# Power.net
KiCad netlist of a schematic drawn in Altium Designer
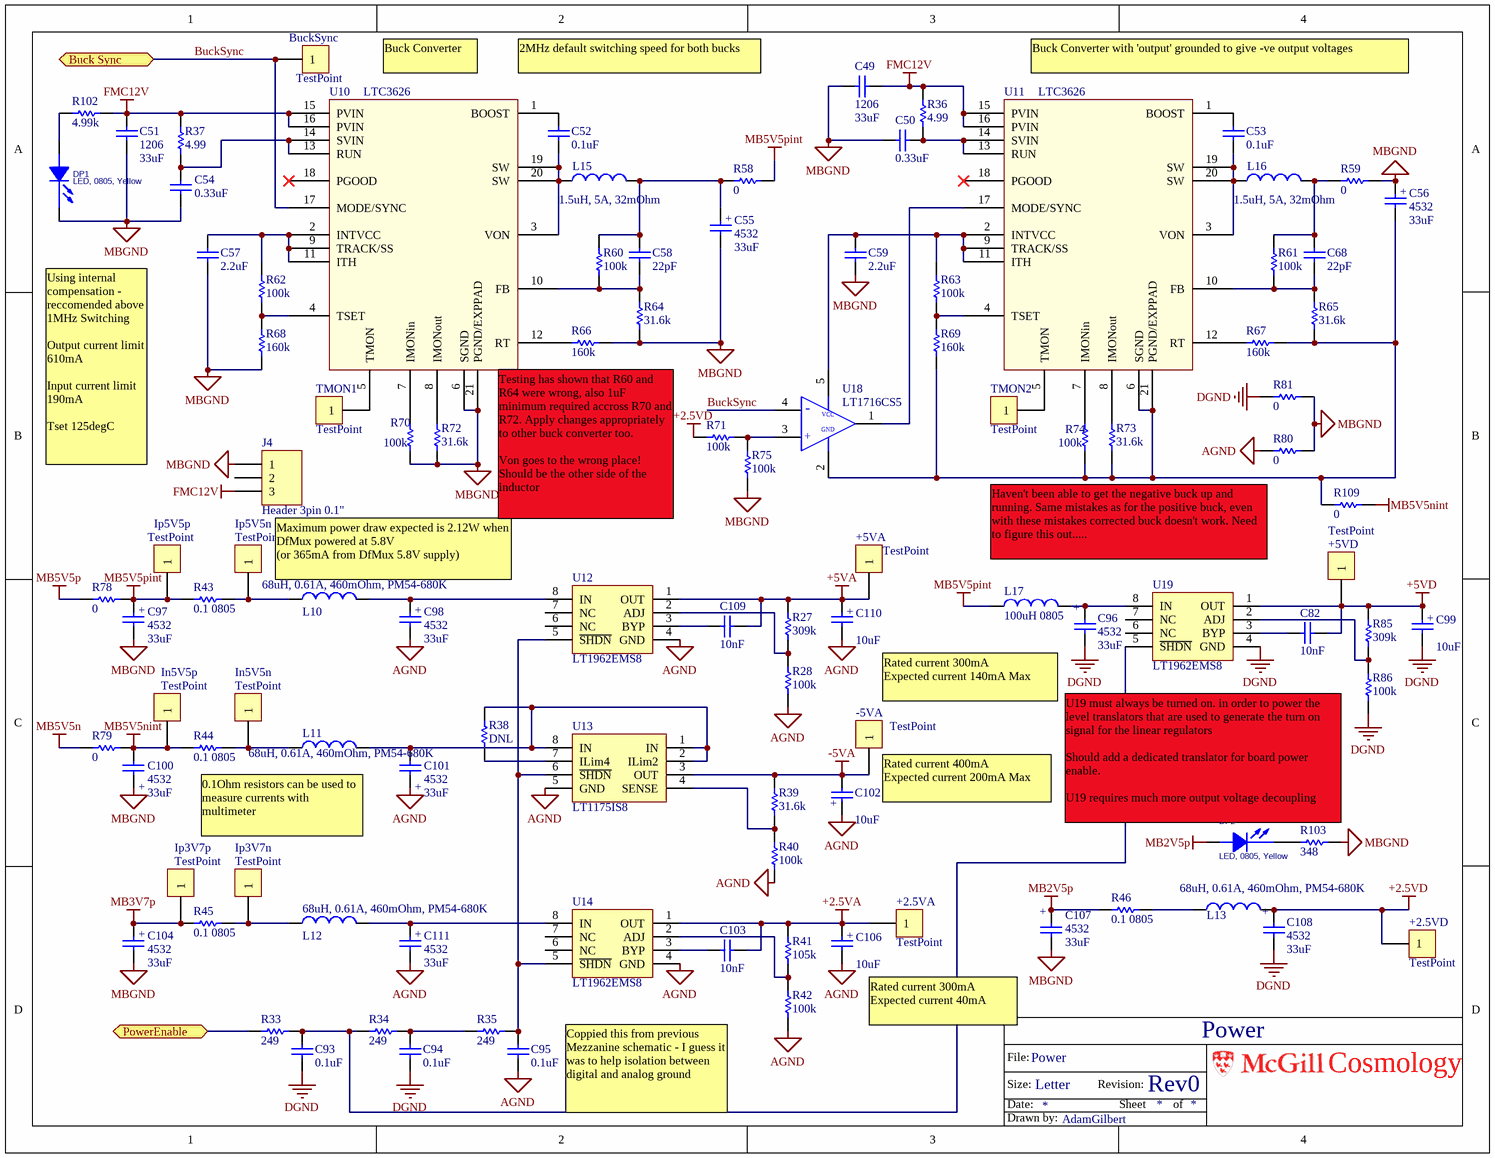
[diagram p0: Power.SchDoc]

(export (version "E")
  (design (tool "Eeschema 10.0.6"))
  (components
    (comp (ref "+2.5VA")
      (value "TestPoint")
      (footprint "TP-3520-SK")
      (description "TestPoint1")
      (libsource (lib "") (part "TestPoint_2"))
    )
    (comp (ref "+2.5VD")
      (value "TestPoint")
      (footprint "TP-3520-SK")
      (description "TestPoint1")
      (libsource (lib "") (part "TestPoint_2"))
    )
    (comp (ref "+5VA")
      (value "TestPoint")
      (footprint "TP-3520-SK")
      (description "TestPoint1")
      (libsource (lib "MGMEZZ04") (part "TestPoint"))
    )
    (comp (ref "+5VD")
      (value "TestPoint")
      (footprint "TP-3520-SK")
      (description "TestPoint1")
      (libsource (lib "MGMEZZ04") (part "TestPoint"))
    )
    (comp (ref "-5VA")
      (value "TestPoint")
      (footprint "TP-3520-SK")
      (description "TestPoint1")
      (libsource (lib "MGMEZZ04") (part "TestPoint"))
    )
    (comp (ref "BuckSync")
      (value "TestPoint")
      (footprint "TP-3520-SK")
      (description "TestPoint1")
      (libsource (lib "") (part "TestPoint_2"))
    )
    (comp (ref "C49")
      (value "33uF")
      (footprint "1206")
      (description "Capacitor, Ceramic, 1210")
      (fields
        (field (name "MANUFACTURER") "TDK Corporation")
        (field (name "MANUFACTURERS PART NUMBER") "C3216X5R1E336M")
      )
      (libsource (lib "MGMEZZ04") (part "CAP 1210"))
    )
    (comp (ref "C50")
      (value "0.33uF")
      (footprint "0603")
      (description "Capacitor, Ceramic, 0603")
      (fields (field (name "MANUFACTURER") "Generic"))
      (libsource (lib "MGMEZZ04") (part "CAP 0603"))
    )
    (comp (ref "C51")
      (value "33uF")
      (footprint "1206")
      (description "Capacitor, Ceramic, 1210")
      (fields
        (field (name "MANUFACTURER") "TDK Corporation")
        (field (name "MANUFACTURERS PART NUMBER") "C3216X5R1E336M")
      )
      (libsource (lib "MGMEZZ04") (part "CAP 1210"))
    )
    (comp (ref "C52")
      (value "0.1uF")
      (footprint "0603")
      (description "Capacitor, Ceramic, 0603")
      (fields (field (name "MANUFACTURER") "Generic"))
      (libsource (lib "MGMEZZ04") (part "CAP 0603"))
    )
    (comp (ref "C53")
      (value "0.1uF")
      (footprint "0603")
      (description "Capacitor, Ceramic, 0603")
      (fields (field (name "MANUFACTURER") "Generic"))
      (libsource (lib "MGMEZZ04") (part "CAP 0603"))
    )
    (comp (ref "C54")
      (value "0.33uF")
      (footprint "0603")
      (description "Capacitor, Ceramic, 0603")
      (fields (field (name "MANUFACTURER") "Generic"))
      (libsource (lib "MGMEZZ04") (part "CAP 0603"))
    )
    (comp (ref "C55")
      (value "33uF")
      (footprint "4532")
      (description "33u, 16V, 20%, 4532C, X5R")
      (fields
        (field (name "MANUFACTURER") "TDK Corporation")
        (field (name "MANUFACTURERS PART NUMBER") "C4532X5R1C336M")
      )
      (libsource (lib "MGMEZZ04") (part "CAP4532"))
    )
    (comp (ref "C56")
      (value "33uF")
      (footprint "4532")
      (description "33u, 16V, 20%, 4532C, X5R")
      (fields
        (field (name "MANUFACTURER") "TDK Corporation")
        (field (name "MANUFACTURERS PART NUMBER") "C4532X5R1C336M")
      )
      (libsource (lib "MGMEZZ04") (part "CAP4532"))
    )
    (comp (ref "C57")
      (value "2.2uF")
      (footprint "0603")
      (description "Capacitor, Ceramic, 0603")
      (fields (field (name "MANUFACTURER") "Generic"))
      (libsource (lib "MGMEZZ04") (part "CAP 0603"))
    )
    (comp (ref "C58")
      (value "22pF")
      (footprint "0603")
      (description "Capacitor, Ceramic, 0603")
      (fields (field (name "MANUFACTURER") "Generic"))
      (libsource (lib "MGMEZZ04") (part "CAP 0603"))
    )
    (comp (ref "C59")
      (value "2.2uF")
      (footprint "0603")
      (description "Capacitor, Ceramic, 0603")
      (fields (field (name "MANUFACTURER") "Generic"))
      (libsource (lib "MGMEZZ04") (part "CAP 0603"))
    )
    (comp (ref "C68")
      (value "22pF")
      (footprint "0603")
      (description "Capacitor, Ceramic, 0603")
      (fields (field (name "MANUFACTURER") "Generic"))
      (libsource (lib "MGMEZZ04") (part "CAP 0603"))
    )
    (comp (ref "C82")
      (value "10nF")
      (footprint "0603")
      (description "Capacitor, Ceramic, 0603")
      (fields (field (name "MANUFACTURER") "Generic"))
      (libsource (lib "MGMEZZ04") (part "CAP 0603"))
    )
    (comp (ref "C93")
      (value "0.1uF")
      (footprint "0603")
      (description "Capacitor, Ceramic, 0603")
      (fields (field (name "MANUFACTURER") "Generic"))
      (libsource (lib "MGMEZZ04") (part "CAP 0603"))
    )
    (comp (ref "C94")
      (value "0.1uF")
      (footprint "0603")
      (description "Capacitor, Ceramic, 0603")
      (fields (field (name "MANUFACTURER") "Generic"))
      (libsource (lib "MGMEZZ04") (part "CAP 0603"))
    )
    (comp (ref "C95")
      (value "0.1uF")
      (footprint "0603")
      (description "Capacitor, Ceramic, 0603")
      (fields (field (name "MANUFACTURER") "Generic"))
      (libsource (lib "MGMEZZ04") (part "CAP 0603"))
    )
    (comp (ref "C96")
      (value "33uF")
      (footprint "4532")
      (description "33u, 16V, 20%, 4532C, X5R")
      (fields
        (field (name "MANUFACTURER") "TDK Corporation")
        (field (name "MANUFACTURERS PART NUMBER") "C4532X5R1C336M")
      )
      (libsource (lib "MGMEZZ04") (part "CAP4532"))
    )
    (comp (ref "C97")
      (value "33uF")
      (footprint "4532")
      (description "33u, 16V, 20%, 4532C, X5R")
      (fields
        (field (name "MANUFACTURER") "TDK Corporation")
        (field (name "MANUFACTURERS PART NUMBER") "C4532X5R1C336M")
      )
      (libsource (lib "MGMEZZ04") (part "CAP4532"))
    )
    (comp (ref "C98")
      (value "33uF")
      (footprint "4532")
      (description "33u, 16V, 20%, 4532C, X5R")
      (fields
        (field (name "MANUFACTURER") "TDK Corporation")
        (field (name "MANUFACTURERS PART NUMBER") "C4532X5R1C336M")
      )
      (libsource (lib "MGMEZZ04") (part "CAP4532"))
    )
    (comp (ref "C99")
      (value "10uF")
      (footprint "TCASE-A")
      (description "TantA Cap")
      (fields (field (name "MANUFACTURER") "Generic"))
      (libsource (lib "MGMEZZ04") (part "CAP TANT CASE-A"))
    )
    (comp (ref "C100")
      (value "33uF")
      (footprint "4532")
      (description "33u, 16V, 20%, 4532C, X5R")
      (fields
        (field (name "MANUFACTURER") "TDK Corporation")
        (field (name "MANUFACTURERS PART NUMBER") "C4532X5R1C336M")
      )
      (libsource (lib "MGMEZZ04") (part "CAP4532"))
    )
    (comp (ref "C101")
      (value "33uF")
      (footprint "4532")
      (description "33u, 16V, 20%, 4532C, X5R")
      (fields
        (field (name "MANUFACTURER") "TDK Corporation")
        (field (name "MANUFACTURERS PART NUMBER") "C4532X5R1C336M")
      )
      (libsource (lib "MGMEZZ04") (part "CAP4532"))
    )
    (comp (ref "C102")
      (value "10uF")
      (footprint "TCASE-A")
      (description "TantA Cap")
      (fields (field (name "MANUFACTURER") "Generic"))
      (libsource (lib "MGMEZZ04") (part "CAP TANT CASE-A"))
    )
    (comp (ref "C103")
      (value "10nF")
      (footprint "0603")
      (description "Capacitor, Ceramic, 0603")
      (fields (field (name "MANUFACTURER") "Generic"))
      (libsource (lib "MGMEZZ04") (part "CAP 0603"))
    )
    (comp (ref "C104")
      (value "33uF")
      (footprint "4532")
      (description "33u, 16V, 20%, 4532C, X5R")
      (fields
        (field (name "MANUFACTURER") "TDK Corporation")
        (field (name "MANUFACTURERS PART NUMBER") "C4532X5R1C336M")
      )
      (libsource (lib "MGMEZZ04") (part "CAP4532"))
    )
    (comp (ref "C106")
      (value "10uF")
      (footprint "TCASE-A")
      (description "TantA Cap")
      (fields (field (name "MANUFACTURER") "Generic"))
      (libsource (lib "MGMEZZ04") (part "CAP TANT CASE-A"))
    )
    (comp (ref "C107")
      (value "33uF")
      (footprint "4532")
      (description "33u, 16V, 20%, 4532C, X5R")
      (fields
        (field (name "MANUFACTURER") "TDK Corporation")
        (field (name "MANUFACTURERS PART NUMBER") "C4532X5R1C336M")
      )
      (libsource (lib "MGMEZZ04") (part "CAP4532"))
    )
    (comp (ref "C108")
      (value "33uF")
      (footprint "4532")
      (description "33u, 16V, 20%, 4532C, X5R")
      (fields
        (field (name "MANUFACTURER") "TDK Corporation")
        (field (name "MANUFACTURERS PART NUMBER") "C4532X5R1C336M")
      )
      (libsource (lib "MGMEZZ04") (part "CAP4532"))
    )
    (comp (ref "C109")
      (value "10nF")
      (footprint "0603")
      (description "Capacitor, Ceramic, 0603")
      (fields (field (name "MANUFACTURER") "Generic"))
      (libsource (lib "MGMEZZ04") (part "CAP 0603"))
    )
    (comp (ref "C110")
      (value "10uF")
      (footprint "TCASE-A")
      (description "TantA Cap")
      (fields (field (name "MANUFACTURER") "Generic"))
      (libsource (lib "MGMEZZ04") (part "CAP TANT CASE-A"))
    )
    (comp (ref "C111")
      (value "33uF")
      (footprint "4532")
      (description "33u, 16V, 20%, 4532C, X5R")
      (fields
        (field (name "MANUFACTURER") "TDK Corporation")
        (field (name "MANUFACTURERS PART NUMBER") "C4532X5R1C336M")
      )
      (libsource (lib "MGMEZZ04") (part "CAP4532"))
    )
    (comp (ref "DP1")
      (value "LED, 0805, Yellow")
      (description "LED")
      (fields
        (field (name "MANUFACTURER") "Rohm Semiconductor")
        (field (name "MANUFACTURERS PART NUMBER") "SML-211YTT86")
      )
      (libsource (lib "MGMEZZ04") (part "LED, yellow, 0805, 2mA"))
    )
    (comp (ref "DP2")
      (value "LED, 0805, Yellow")
      (description "LED")
      (fields
        (field (name "MANUFACTURER") "Rohm Semiconductor")
        (field (name "MANUFACTURERS PART NUMBER") "SML-211YTT86")
      )
      (libsource (lib "MGMEZZ04") (part "LED, yellow, 0805, 2mA"))
    )
    (comp (ref "In5V5n")
      (value "TestPoint")
      (footprint "TP-3520-SK")
      (description "TestPoint1")
      (libsource (lib "MGMEZZ04") (part "TestPoint"))
    )
    (comp (ref "In5V5p")
      (value "TestPoint")
      (footprint "TP-3520-SK")
      (description "TestPoint1")
      (libsource (lib "MGMEZZ04") (part "TestPoint"))
    )
    (comp (ref "Ip3V7n")
      (value "TestPoint")
      (footprint "TP-3520-SK")
      (description "TestPoint1")
      (libsource (lib "MGMEZZ04") (part "TestPoint"))
    )
    (comp (ref "Ip3V7p")
      (value "TestPoint")
      (footprint "TP-3520-SK")
      (description "TestPoint1")
      (libsource (lib "MGMEZZ04") (part "TestPoint"))
    )
    (comp (ref "Ip5V5n")
      (value "TestPoint")
      (footprint "TP-3520-SK")
      (description "TestPoint1")
      (libsource (lib "MGMEZZ04") (part "TestPoint"))
    )
    (comp (ref "Ip5V5p")
      (value "TestPoint")
      (footprint "TP-3520-SK")
      (description "TestPoint1")
      (libsource (lib "MGMEZZ04") (part "TestPoint"))
    )
    (comp (ref "J4")
      (value "Header 3pin 0.1\"")
      (footprint "HDR1X3_MolexVertical")
      (description "Header, 0.1\"  3-Pin")
      (fields (field (name "MANUFACTURER") "Molex") (field (name "MANUFACTURERS PART NUMBER") "0099990987"))
      (libsource (lib "MGMEZZ04") (part "Header 3"))
    )
    (comp (ref "L10")
      (value "68uH")
      (footprint "CHOKEPM54")
      (description "Inductor PM54")
      (fields
        (field (name "MANUFACTURER") "Bourns Inc.")
        (field (name "MANUFACTURERS PART NUMBER") "PM54-680K")
        (field (name "PART CONSTRAINTS") "68uH, 0.61A, 460mOhm, PM54-680K")
      )
      (libsource (lib "MGMEZZ04") (part "INDPM54"))
    )
    (comp (ref "L11")
      (value "68uH")
      (footprint "CHOKEPM54")
      (description "Inductor PM54")
      (fields
        (field (name "MANUFACTURER") "Bourns Inc.")
        (field (name "MANUFACTURERS PART NUMBER") "PM54-680K")
        (field (name "PART CONSTRAINTS") "68uH, 0.61A, 460mOhm, PM54-680K")
      )
      (libsource (lib "") (part "INDPM54_1"))
    )
    (comp (ref "L12")
      (value "68uH")
      (footprint "CHOKEPM54")
      (description "Inductor PM54")
      (fields
        (field (name "MANUFACTURER") "Bourns Inc.")
        (field (name "MANUFACTURERS PART NUMBER") "PM54-680K")
        (field (name "PART CONSTRAINTS") "68uH, 0.61A, 460mOhm, PM54-680K")
      )
      (libsource (lib "MGMEZZ04") (part "INDPM54"))
    )
    (comp (ref "L13")
      (value "68uH")
      (footprint "CHOKEPM54")
      (description "Inductor PM54")
      (fields
        (field (name "MANUFACTURER") "Bourns Inc.")
        (field (name "MANUFACTURERS PART NUMBER") "PM54-680K")
        (field (name "PART CONSTRAINTS") "68uH, 0.61A, 460mOhm, PM54-680K")
      )
      (libsource (lib "") (part "INDPM54_1"))
    )
    (comp (ref "L15")
      (value "1.5uH")
      (footprint "IHLP-1212")
      (description "Inductor IHLP1212")
      (fields
        (field (name "MANUFACTURER") "Vishay Dale")
        (field (name "MANUFACTURERS PART NUMBER") "IHLP1212BZER1R5M11")
        (field (name "PART CONSTRAINTS") "1.5uH, 5A, 32mOhm")
      )
      (libsource (lib "MGMEZZ04") (part "IND IHLP1212"))
    )
    (comp (ref "L16")
      (value "1.5uH")
      (footprint "IHLP-1212")
      (description "Inductor IHLP1212")
      (fields
        (field (name "MANUFACTURER") "Vishay Dale")
        (field (name "MANUFACTURERS PART NUMBER") "IHLP1212BZER1R5M11")
        (field (name "PART CONSTRAINTS") "1.5uH, 5A, 32mOhm")
      )
      (libsource (lib "MGMEZZ04") (part "IND IHLP1212"))
    )
    (comp (ref "L17")
      (value "100uH 0805")
      (footprint "0805")
      (description "Inductor 0805")
      (fields
        (field (name "MANUFACTURER") "TDK Corporation")
        (field (name "MANUFACTURERS PART NUMBER") "GLCR2012T101M-HC")
      )
      (libsource (lib "MGMEZZ04") (part "IND 0805"))
    )
    (comp (ref "R27")
      (value "309k")
      (footprint "0603")
      (description "Resistor")
      (fields (field (name "MANUFACTURER") "Generic"))
      (libsource (lib "MGMEZZ04") (part "RES 0603"))
    )
    (comp (ref "R28")
      (value "100k")
      (footprint "0603")
      (description "Resistor")
      (fields (field (name "MANUFACTURER") "Generic"))
      (libsource (lib "MGMEZZ04") (part "RES 0603"))
    )
    (comp (ref "R33")
      (value "249")
      (footprint "0603")
      (description "Resistor")
      (fields (field (name "MANUFACTURER") "Generic"))
      (libsource (lib "MGMEZZ04") (part "RES 0603"))
    )
    (comp (ref "R34")
      (value "249")
      (footprint "0603")
      (description "Resistor")
      (fields (field (name "MANUFACTURER") "Generic"))
      (libsource (lib "MGMEZZ04") (part "RES 0603"))
    )
    (comp (ref "R35")
      (value "249")
      (footprint "0603")
      (description "Resistor")
      (fields (field (name "MANUFACTURER") "Generic"))
      (libsource (lib "MGMEZZ04") (part "RES 0603"))
    )
    (comp (ref "R36")
      (value "4.99")
      (footprint "0603")
      (description "Resistor")
      (fields (field (name "MANUFACTURER") "Generic"))
      (libsource (lib "MGMEZZ04") (part "RES 0603"))
    )
    (comp (ref "R37")
      (value "4.99")
      (footprint "0603")
      (description "Resistor")
      (fields (field (name "MANUFACTURER") "Generic"))
      (libsource (lib "MGMEZZ04") (part "RES 0603"))
    )
    (comp (ref "R38")
      (value "DNL")
      (footprint "0603")
      (description "Resistor")
      (fields (field (name "MANUFACTURER") "Generic"))
      (libsource (lib "MGMEZZ04") (part "RES 0603"))
    )
    (comp (ref "R39")
      (value "31.6k")
      (footprint "0603")
      (description "Resistor")
      (fields (field (name "MANUFACTURER") "Generic"))
      (libsource (lib "MGMEZZ04") (part "RES 0603"))
    )
    (comp (ref "R40")
      (value "100k")
      (footprint "0603")
      (description "Resistor")
      (fields (field (name "MANUFACTURER") "Generic"))
      (libsource (lib "MGMEZZ04") (part "RES 0603"))
    )
    (comp (ref "R41")
      (value "105k")
      (footprint "0603")
      (description "Resistor")
      (fields (field (name "MANUFACTURER") "Generic"))
      (libsource (lib "MGMEZZ04") (part "RES 0603"))
    )
    (comp (ref "R42")
      (value "100k")
      (footprint "0603")
      (description "Resistor")
      (fields (field (name "MANUFACTURER") "Generic"))
      (libsource (lib "MGMEZZ04") (part "RES 0603"))
    )
    (comp (ref "R43")
      (value "0.1 0805")
      (footprint "0805")
      (description "RES 0.1 OHM 1/8W 0805 SMD")
      (fields
        (field (name "MANUFACTURER") "Panasonic Electronic Components")
        (field (name "MANUFACTURERS PART NUMBER") "ERJ-L06KF10CV")
      )
      (libsource (lib "MGMEZZ04") (part "RES 0805"))
    )
    (comp (ref "R44")
      (value "0.1 0805")
      (footprint "0805")
      (description "RES 0.1 OHM 1/8W 0805 SMD")
      (fields
        (field (name "MANUFACTURER") "Panasonic Electronic Components")
        (field (name "MANUFACTURERS PART NUMBER") "ERJ-L06KF10CV")
      )
      (libsource (lib "MGMEZZ04") (part "RES 0805"))
    )
    (comp (ref "R45")
      (value "0.1 0805")
      (footprint "0805")
      (description "RES 0.1 OHM 1/8W 0805 SMD")
      (fields
        (field (name "MANUFACTURER") "Panasonic Electronic Components")
        (field (name "MANUFACTURERS PART NUMBER") "ERJ-L06KF10CV")
      )
      (libsource (lib "MGMEZZ04") (part "RES 0805"))
    )
    (comp (ref "R46")
      (value "0.1 0805")
      (footprint "0805")
      (description "RES 0.1 OHM 1/8W 0805 SMD")
      (fields
        (field (name "MANUFACTURER") "Panasonic Electronic Components")
        (field (name "MANUFACTURERS PART NUMBER") "ERJ-L06KF10CV")
      )
      (libsource (lib "MGMEZZ04") (part "RES 0805"))
    )
    (comp (ref "R58")
      (value "0")
      (footprint "0805")
      (description "RES 0.0 OHM 1/8W 0805 SMD")
      (fields (field (name "MANUFACTURER") "Generic"))
      (libsource (lib "MGMEZZ04") (part "RES 0805"))
    )
    (comp (ref "R59")
      (value "0")
      (footprint "0805")
      (description "RES 0.0 OHM 1/8W 0805 SMD")
      (fields (field (name "MANUFACTURER") "Generic"))
      (libsource (lib "MGMEZZ04") (part "RES 0805"))
    )
    (comp (ref "R60")
      (value "100k")
      (footprint "0603")
      (description "Resistor")
      (fields (field (name "MANUFACTURER") "Generic"))
      (libsource (lib "MGMEZZ04") (part "RES 0603"))
    )
    (comp (ref "R61")
      (value "100k")
      (footprint "0603")
      (description "Resistor")
      (fields (field (name "MANUFACTURER") "Generic"))
      (libsource (lib "MGMEZZ04") (part "RES 0603"))
    )
    (comp (ref "R62")
      (value "100k")
      (footprint "0603")
      (description "Resistor")
      (fields (field (name "MANUFACTURER") "Generic"))
      (libsource (lib "MGMEZZ04") (part "RES 0603"))
    )
    (comp (ref "R63")
      (value "100k")
      (footprint "0603")
      (description "Resistor")
      (fields (field (name "MANUFACTURER") "Generic"))
      (libsource (lib "MGMEZZ04") (part "RES 0603"))
    )
    (comp (ref "R64")
      (value "31.6k")
      (footprint "0603")
      (description "Resistor")
      (fields (field (name "MANUFACTURER") "Generic"))
      (libsource (lib "MGMEZZ04") (part "RES 0603"))
    )
    (comp (ref "R65")
      (value "31.6k")
      (footprint "0603")
      (description "Resistor")
      (fields (field (name "MANUFACTURER") "Generic"))
      (libsource (lib "MGMEZZ04") (part "RES 0603"))
    )
    (comp (ref "R66")
      (value "160k")
      (footprint "0603")
      (description "Resistor")
      (fields (field (name "MANUFACTURER") "Generic"))
      (libsource (lib "MGMEZZ04") (part "RES 0603"))
    )
    (comp (ref "R67")
      (value "160k")
      (footprint "0603")
      (description "Resistor")
      (fields (field (name "MANUFACTURER") "Generic"))
      (libsource (lib "MGMEZZ04") (part "RES 0603"))
    )
    (comp (ref "R68")
      (value "160k")
      (footprint "0603")
      (description "Resistor")
      (fields (field (name "MANUFACTURER") "Generic"))
      (libsource (lib "MGMEZZ04") (part "RES 0603"))
    )
    (comp (ref "R69")
      (value "160k")
      (footprint "0603")
      (description "Resistor")
      (fields (field (name "MANUFACTURER") "Generic"))
      (libsource (lib "MGMEZZ04") (part "RES 0603"))
    )
    (comp (ref "R70")
      (value "100k")
      (footprint "0603")
      (description "Resistor")
      (fields (field (name "MANUFACTURER") "Generic"))
      (libsource (lib "MGMEZZ04") (part "RES 0603"))
    )
    (comp (ref "R71")
      (value "100k")
      (footprint "0603")
      (description "Resistor")
      (fields (field (name "MANUFACTURER") "Generic"))
      (libsource (lib "MGMEZZ04") (part "RES 0603"))
    )
    (comp (ref "R72")
      (value "31.6k")
      (footprint "0603")
      (description "Resistor")
      (fields (field (name "MANUFACTURER") "Generic"))
      (libsource (lib "MGMEZZ04") (part "RES 0603"))
    )
    (comp (ref "R73")
      (value "31.6k")
      (footprint "0603")
      (description "Resistor")
      (fields (field (name "MANUFACTURER") "Generic"))
      (libsource (lib "MGMEZZ04") (part "RES 0603"))
    )
    (comp (ref "R74")
      (value "100k")
      (footprint "0603")
      (description "Resistor")
      (fields (field (name "MANUFACTURER") "Generic"))
      (libsource (lib "MGMEZZ04") (part "RES 0603"))
    )
    (comp (ref "R75")
      (value "100k")
      (footprint "0603")
      (description "Resistor")
      (fields (field (name "MANUFACTURER") "Generic"))
      (libsource (lib "MGMEZZ04") (part "RES 0603"))
    )
    (comp (ref "R78")
      (value "0")
      (footprint "0805")
      (description "RES 0.0 OHM 1/8W 0805 SMD")
      (fields (field (name "MANUFACTURER") "Generic"))
      (libsource (lib "MGMEZZ04") (part "RES 0805"))
    )
    (comp (ref "R79")
      (value "0")
      (footprint "0805")
      (description "RES 0.0 OHM 1/8W 0805 SMD")
      (fields (field (name "MANUFACTURER") "Generic"))
      (libsource (lib "MGMEZZ04") (part "RES 0805"))
    )
    (comp (ref "R80")
      (value "0")
      (footprint "1206")
      (description "RES 0.0 OHM 1/8W 1206 SMD")
      (fields (field (name "MANUFACTURER") "Generic"))
      (libsource (lib "MGMEZZ04") (part "RES 1206"))
    )
    (comp (ref "R81")
      (value "0")
      (footprint "1206")
      (description "RES 0.0 OHM 1/8W 1206 SMD")
      (fields (field (name "MANUFACTURER") "Generic"))
      (libsource (lib "MGMEZZ04") (part "RES 1206"))
    )
    (comp (ref "R85")
      (value "309k")
      (footprint "0603")
      (description "Resistor")
      (fields (field (name "MANUFACTURER") "Generic"))
      (libsource (lib "MGMEZZ04") (part "RES 0603"))
    )
    (comp (ref "R86")
      (value "100k")
      (footprint "0603")
      (description "Resistor")
      (fields (field (name "MANUFACTURER") "Generic"))
      (libsource (lib "MGMEZZ04") (part "RES 0603"))
    )
    (comp (ref "R102")
      (value "4.99k")
      (footprint "0603")
      (description "Resistor")
      (fields (field (name "MANUFACTURER") "Generic"))
      (libsource (lib "MGMEZZ04") (part "RES 0603"))
    )
    (comp (ref "R103")
      (value "348")
      (footprint "0603")
      (description "Resistor")
      (fields (field (name "MANUFACTURER") "Generic"))
      (libsource (lib "MGMEZZ04") (part "RES 0603"))
    )
    (comp (ref "R109")
      (value "0")
      (footprint "0805")
      (description "RES 0.0 OHM 1/8W 0805 SMD")
      (fields (field (name "MANUFACTURER") "Generic"))
      (libsource (lib "MGMEZZ04") (part "RES 0805"))
    )
    (comp (ref "TMON1")
      (value "TestPoint")
      (footprint "TP-3520-SK")
      (description "TestPoint1")
      (libsource (lib "") (part "TestPoint_1"))
    )
    (comp (ref "TMON2")
      (value "TestPoint")
      (footprint "TP-3520-SK")
      (description "TestPoint1")
      (libsource (lib "") (part "TestPoint_1"))
    )
    (comp (ref "U10")
      (value "LTC3626")
      (footprint "LTC3626")
      (description "20V, 2.5A Sync buck, 3Mhz")
      (fields
        (field (name "MANUFACTURERS PART NUMBER") "LTC3626EUDC#PBF")
        (field (name "MANUFACTURER") "Linear Technology")
      )
      (libsource (lib "MGMEZZ04") (part "LTC3626"))
    )
    (comp (ref "U11")
      (value "LTC3626")
      (footprint "LTC3626")
      (description "20V, 2.5A Sync buck, 3Mhz")
      (fields
        (field (name "MANUFACTURERS PART NUMBER") "LTC3626EUDC#PBF")
        (field (name "MANUFACTURER") "Linear Technology")
      )
      (libsource (lib "MGMEZZ04") (part "LTC3626"))
    )
    (comp (ref "U12")
      (value "LT1962EMS8")
      (footprint "MSOP-8")
      (description "REG, micropower, low noise, low  dropout")
      (fields
        (field (name "MANUFACTURER") "Linear Technology")
        (field (name "MANUFACTURERS PART NUMBER") "LT1962EMS8#PBF")
      )
      (libsource (lib "MGMEZZ04") (part "LT1962EMS8"))
    )
    (comp (ref "U13")
      (value "LT1175IS8")
      (footprint "SO8")
      (description "REG, negative micropower low dropout")
      (fields
        (field (name "MANUFACTURER") "Linear Technology")
        (field (name "MANUFACTURERS PART NUMBER") "LT1175IS8#PBF")
      )
      (libsource (lib "MGMEZZ04") (part "LT1175IS8"))
    )
    (comp (ref "U14")
      (value "LT1962EMS8")
      (footprint "MSOP-8")
      (description "REG, micropower, low noise, low  dropout")
      (fields
        (field (name "MANUFACTURER") "Linear Technology")
        (field (name "MANUFACTURERS PART NUMBER") "LT1962EMS8#PBF")
      )
      (libsource (lib "MGMEZZ04") (part "LT1962EMS8"))
    )
    (comp (ref "U18")
      (value "LT1716CS5")
      (footprint "SOT23-5")
      (description "Comparator 2.7V to 44V rail to rail")
      (fields
        (field (name "MANUFACTURER") "Linear Technology")
        (field (name "MANUFACTURERS PART NUMBER") "LT1716CS5#TRMPBF")
      )
      (libsource (lib "MGMEZZ04") (part "LT1716CS5"))
    )
    (comp (ref "U19")
      (value "LT1962EMS8")
      (footprint "MSOP-8")
      (description "REG, micropower, low noise, low  dropout")
      (fields
        (field (name "MANUFACTURER") "Linear Technology")
        (field (name "MANUFACTURERS PART NUMBER") "LT1962EMS8#PBF")
      )
      (libsource (lib "MGMEZZ04") (part "LT1962EMS8"))
    )
  )
  (nets
    (net (code "1") (name "+2.5VA") (class "Default")
      (node (ref "+2.5VA") (pin "1") (pinfunction "1_1") (pintype "passive"))
      (node (ref "C103") (pin "2") (pinfunction "2_2") (pintype "passive"))
      (node (ref "C106") (pin "1") (pinfunction "1_1") (pintype "passive"))
      (node (ref "R41") (pin "1") (pinfunction "1_1") (pintype "passive"))
      (node (ref "U14") (pin "1") (pinfunction "OUT_1") (pintype "power_in"))
    )
    (net (code "2") (name "+2.5VD") (class "Default")
      (node (ref "+2.5VD") (pin "1") (pinfunction "1_1") (pintype "passive"))
      (node (ref "C108") (pin "1") (pinfunction "1_1") (pintype "passive"))
      (node (ref "L13") (pin "1") (pinfunction "1_1") (pintype "passive"))
      (node (ref "R71") (pin "2") (pinfunction "2_2") (pintype "passive"))
    )
    (net (code "3") (name "+5VA") (class "Default")
      (node (ref "+5VA") (pin "1") (pinfunction "1_1") (pintype "passive"))
      (node (ref "C109") (pin "2") (pinfunction "2_2") (pintype "passive"))
      (node (ref "C110") (pin "1") (pinfunction "1_1") (pintype "passive"))
      (node (ref "R27") (pin "1") (pinfunction "1_1") (pintype "passive"))
      (node (ref "U12") (pin "1") (pinfunction "OUT_1") (pintype "power_in"))
    )
    (net (code "4") (name "+5VD") (class "Default")
      (node (ref "+5VD") (pin "1") (pinfunction "1_1") (pintype "passive"))
      (node (ref "C82") (pin "2") (pinfunction "2_2") (pintype "passive"))
      (node (ref "C99") (pin "1") (pinfunction "1_1") (pintype "passive"))
      (node (ref "R85") (pin "1") (pinfunction "1_1") (pintype "passive"))
      (node (ref "U19") (pin "1") (pinfunction "OUT_1") (pintype "power_in"))
    )
    (net (code "5") (name "-5VA") (class "Default")
      (node (ref "-5VA") (pin "1") (pinfunction "1_1") (pintype "passive"))
      (node (ref "C102") (pin "2") (pinfunction "2_2") (pintype "passive"))
      (node (ref "R39") (pin "1") (pinfunction "1_1") (pintype "passive"))
      (node (ref "U13") (pin "3") (pinfunction "OUT_3") (pintype "passive"))
    )
    (net (code "6") (name "/BuckSync") (class "Default")
      (node (ref "BuckSync") (pin "1") (pinfunction "1_1") (pintype "passive"))
      (node (ref "U10") (pin "17") (pinfunction "MODE/SYNC_17") (pintype "passive"))
      (node (ref "U18") (pin "4") (pinfunction "-_4") (pintype "power_in"))
    )
    (net (code "7") (name "/PowerEnable") (class "Default")
      (node (ref "R33") (pin "1") (pinfunction "1_1") (pintype "passive"))
    )
    (net (code "8") (name "AGND") (class "Default")
      (node (ref "C101") (pin "1") (pinfunction "1_1") (pintype "passive"))
      (node (ref "C102") (pin "1") (pinfunction "1_1") (pintype "passive"))
      (node (ref "C106") (pin "2") (pinfunction "2_2") (pintype "passive"))
      (node (ref "C110") (pin "2") (pinfunction "2_2") (pintype "passive"))
      (node (ref "C111") (pin "2") (pinfunction "2_2") (pintype "passive"))
      (node (ref "C95") (pin "2") (pinfunction "2_2") (pintype "passive"))
      (node (ref "C98") (pin "2") (pinfunction "2_2") (pintype "passive"))
      (node (ref "R28") (pin "2") (pinfunction "2_2") (pintype "passive"))
      (node (ref "R40") (pin "2") (pinfunction "2_2") (pintype "passive"))
      (node (ref "R42") (pin "2") (pinfunction "2_2") (pintype "passive"))
      (node (ref "R80") (pin "2") (pinfunction "2_2") (pintype "passive"))
      (node (ref "U12") (pin "4") (pinfunction "GND_4") (pintype "power_in"))
      (node (ref "U13") (pin "5") (pinfunction "GND_5") (pintype "passive"))
      (node (ref "U14") (pin "4") (pinfunction "GND_4") (pintype "power_in"))
    )
    (net (code "9") (name "DGND") (class "Default")
      (node (ref "C108") (pin "2") (pinfunction "2_2") (pintype "passive"))
      (node (ref "C93") (pin "1") (pinfunction "1_1") (pintype "passive"))
      (node (ref "C94") (pin "2") (pinfunction "2_2") (pintype "passive"))
      (node (ref "C96") (pin "2") (pinfunction "2_2") (pintype "passive"))
      (node (ref "C99") (pin "2") (pinfunction "2_2") (pintype "passive"))
      (node (ref "R81") (pin "2") (pinfunction "2_2") (pintype "passive"))
      (node (ref "R86") (pin "2") (pinfunction "2_2") (pintype "passive"))
      (node (ref "U19") (pin "4") (pinfunction "GND_4") (pintype "power_in"))
    )
    (net (code "10") (name "FMC12V") (class "Default")
      (node (ref "C49") (pin "1") (pinfunction "1_1") (pintype "passive"))
      (node (ref "C51") (pin "1") (pinfunction "1_1") (pintype "passive"))
      (node (ref "J4") (pin "3") (pinfunction "3_3") (pintype "passive"))
      (node (ref "R102") (pin "2") (pinfunction "2_2") (pintype "passive"))
      (node (ref "R36") (pin "2") (pinfunction "2_2") (pintype "passive"))
      (node (ref "R37") (pin "1") (pinfunction "1_1") (pintype "passive"))
      (node (ref "U10") (pin "15") (pinfunction "PVIN_15") (pintype "passive"))
      (node (ref "U10") (pin "16") (pinfunction "PVIN_16") (pintype "passive"))
      (node (ref "U11") (pin "15") (pinfunction "PVIN_15") (pintype "passive"))
      (node (ref "U11") (pin "16") (pinfunction "PVIN_16") (pintype "passive"))
    )
    (net (code "11") (name "MB2V5p") (class "Default")
      (node (ref "C107") (pin "1") (pinfunction "1_1") (pintype "passive"))
      (node (ref "DP2") (pin "1") (pinfunction "ANODE_1") (pintype "passive"))
      (node (ref "R46") (pin "1") (pinfunction "1_1") (pintype "passive"))
    )
    (net (code "12") (name "MB3V7p") (class "Default")
      (node (ref "C104") (pin "1") (pinfunction "1_1") (pintype "passive"))
      (node (ref "Ip3V7p") (pin "1") (pinfunction "1_1") (pintype "passive"))
      (node (ref "R45") (pin "1") (pinfunction "1_1") (pintype "passive"))
    )
    (net (code "13") (name "MB5V5n") (class "Default")
      (node (ref "R79") (pin "1") (pinfunction "1_1") (pintype "passive"))
    )
    (net (code "14") (name "MB5V5nint") (class "Default")
      (node (ref "C100") (pin "2") (pinfunction "2_2") (pintype "passive"))
      (node (ref "In5V5p") (pin "1") (pinfunction "1_1") (pintype "passive"))
      (node (ref "R109") (pin "1") (pinfunction "1_1") (pintype "passive"))
      (node (ref "R44") (pin "1") (pinfunction "1_1") (pintype "passive"))
      (node (ref "R79") (pin "2") (pinfunction "2_2") (pintype "passive"))
    )
    (net (code "15") (name "MB5V5p") (class "Default")
      (node (ref "R78") (pin "1") (pinfunction "1_1") (pintype "passive"))
    )
    (net (code "16") (name "MB5V5pint") (class "Default")
      (node (ref "C97") (pin "1") (pinfunction "1_1") (pintype "passive"))
      (node (ref "Ip5V5p") (pin "1") (pinfunction "1_1") (pintype "passive"))
      (node (ref "L17") (pin "1") (pinfunction "1_1") (pintype "passive"))
      (node (ref "R43") (pin "1") (pinfunction "1_1") (pintype "passive"))
      (node (ref "R58") (pin "2") (pinfunction "2_2") (pintype "passive"))
      (node (ref "R78") (pin "2") (pinfunction "2_2") (pintype "passive"))
    )
    (net (code "17") (name "MBGND") (class "Default")
      (node (ref "C100") (pin "1") (pinfunction "1_1") (pintype "passive"))
      (node (ref "C104") (pin "2") (pinfunction "2_2") (pintype "passive"))
      (node (ref "C107") (pin "2") (pinfunction "2_2") (pintype "passive"))
      (node (ref "C49") (pin "2") (pinfunction "2_2") (pintype "passive"))
      (node (ref "C50") (pin "1") (pinfunction "1_1") (pintype "passive"))
      (node (ref "C51") (pin "2") (pinfunction "2_2") (pintype "passive"))
      (node (ref "C54") (pin "1") (pinfunction "1_1") (pintype "passive"))
      (node (ref "C55") (pin "2") (pinfunction "2_2") (pintype "passive"))
      (node (ref "C56") (pin "1") (pinfunction "1_1") (pintype "passive"))
      (node (ref "C57") (pin "1") (pinfunction "1_1") (pintype "passive"))
      (node (ref "C59") (pin "1") (pinfunction "1_1") (pintype "passive"))
      (node (ref "C97") (pin "2") (pinfunction "2_2") (pintype "passive"))
      (node (ref "DP1") (pin "2") (pinfunction "CATHODE_2") (pintype "passive"))
      (node (ref "J4") (pin "1") (pinfunction "1_1") (pintype "passive"))
      (node (ref "R103") (pin "1") (pinfunction "1_1") (pintype "passive"))
      (node (ref "R59") (pin "2") (pinfunction "2_2") (pintype "passive"))
      (node (ref "R64") (pin "1") (pinfunction "1_1") (pintype "passive"))
      (node (ref "R66") (pin "1") (pinfunction "1_1") (pintype "passive"))
      (node (ref "R68") (pin "2") (pinfunction "2_2") (pintype "passive"))
      (node (ref "R70") (pin "1") (pinfunction "1_1") (pintype "passive"))
      (node (ref "R72") (pin "1") (pinfunction "1_1") (pintype "passive"))
      (node (ref "R75") (pin "2") (pinfunction "2_2") (pintype "passive"))
      (node (ref "R80") (pin "1") (pinfunction "1_1") (pintype "passive"))
      (node (ref "R81") (pin "1") (pinfunction "1_1") (pintype "passive"))
      (node (ref "U10") (pin "21") (pinfunction "PGND/EXPPAD_21") (pintype "passive"))
      (node (ref "U10") (pin "6") (pinfunction "SGND_6") (pintype "passive"))
    )
    (net (code "18") (name "Net-(C55-Pad1)") (class "Default")
      (node (ref "C55") (pin "1") (pinfunction "1_1") (pintype "passive"))
      (node (ref "C58") (pin "2") (pinfunction "2_2") (pintype "passive"))
      (node (ref "L15") (pin "2") (pinfunction "2_2") (pintype "passive"))
      (node (ref "R58") (pin "1") (pinfunction "1_1") (pintype "passive"))
      (node (ref "R60") (pin "2") (pinfunction "2_2") (pintype "passive"))
    )
    (net (code "19") (name "Net-(C68-Pad2)") (class "Default")
      (node (ref "C68") (pin "2") (pinfunction "2_2") (pintype "passive"))
      (node (ref "L16") (pin "2") (pinfunction "2_2") (pintype "passive"))
      (node (ref "R59") (pin "1") (pinfunction "1_1") (pintype "passive"))
      (node (ref "R61") (pin "2") (pinfunction "2_2") (pintype "passive"))
    )
    (net (code "20") (name "Net-(C94-Pad1)") (class "Default")
      (node (ref "C94") (pin "1") (pinfunction "1_1") (pintype "passive"))
      (node (ref "R34") (pin "2") (pinfunction "2_2") (pintype "passive"))
      (node (ref "R35") (pin "1") (pinfunction "1_1") (pintype "passive"))
    )
    (net (code "21") (name "Net-(DP1-ANODE)") (class "Default")
      (node (ref "DP1") (pin "1") (pinfunction "ANODE_1") (pintype "passive"))
      (node (ref "R102") (pin "1") (pinfunction "1_1") (pintype "passive"))
    )
    (net (code "22") (name "Net-(DP2-CATHODE)") (class "Default")
      (node (ref "DP2") (pin "2") (pinfunction "CATHODE_2") (pintype "passive"))
      (node (ref "R103") (pin "2") (pinfunction "2_2") (pintype "passive"))
    )
    (net (code "23") (name "Net-(In5V5n-Pad1)") (class "Default")
      (node (ref "In5V5n") (pin "1") (pinfunction "1_1") (pintype "passive"))
      (node (ref "L11") (pin "2") (pinfunction "2_2") (pintype "passive"))
      (node (ref "R44") (pin "2") (pinfunction "2_2") (pintype "passive"))
    )
    (net (code "24") (name "Net-(Ip3V7n-Pad1)") (class "Default")
      (node (ref "Ip3V7n") (pin "1") (pinfunction "1_1") (pintype "passive"))
      (node (ref "L12") (pin "1") (pinfunction "1_1") (pintype "passive"))
      (node (ref "R45") (pin "2") (pinfunction "2_2") (pintype "passive"))
    )
    (net (code "25") (name "Net-(Ip5V5n-Pad1)") (class "Default")
      (node (ref "Ip5V5n") (pin "1") (pinfunction "1_1") (pintype "passive"))
      (node (ref "L10") (pin "1") (pinfunction "1_1") (pintype "passive"))
      (node (ref "R43") (pin "2") (pinfunction "2_2") (pintype "passive"))
    )
    (net (code "26") (name "Net-(L13-Pad2)") (class "Default")
      (node (ref "L13") (pin "2") (pinfunction "2_2") (pintype "passive"))
      (node (ref "R46") (pin "2") (pinfunction "2_2") (pintype "passive"))
    )
    (net (code "27") (name "Net-(U10-BOOST)") (class "Default")
      (node (ref "C52") (pin "2") (pinfunction "2_2") (pintype "passive"))
      (node (ref "U10") (pin "1") (pinfunction "BOOST_1") (pintype "passive"))
    )
    (net (code "28") (name "Net-(U10-FB)") (class "Default")
      (node (ref "C58") (pin "1") (pinfunction "1_1") (pintype "passive"))
      (node (ref "R60") (pin "1") (pinfunction "1_1") (pintype "passive"))
      (node (ref "R64") (pin "2") (pinfunction "2_2") (pintype "passive"))
      (node (ref "U10") (pin "10") (pinfunction "FB_10") (pintype "passive"))
    )
    (net (code "29") (name "Net-(U10-IMONin)") (class "Default")
      (node (ref "R70") (pin "2") (pinfunction "2_2") (pintype "passive"))
      (node (ref "U10") (pin "7") (pinfunction "IMONin_7") (pintype "passive"))
    )
    (net (code "30") (name "Net-(U10-IMONout)") (class "Default")
      (node (ref "R72") (pin "2") (pinfunction "2_2") (pintype "passive"))
      (node (ref "U10") (pin "8") (pinfunction "IMONout_8") (pintype "passive"))
    )
    (net (code "31") (name "Net-(U10-INTVCC)") (class "Default")
      (node (ref "C57") (pin "2") (pinfunction "2_2") (pintype "passive"))
      (node (ref "R62") (pin "2") (pinfunction "2_2") (pintype "passive"))
      (node (ref "U10") (pin "11") (pinfunction "ITH_11") (pintype "passive"))
      (node (ref "U10") (pin "2") (pinfunction "INTVCC_2") (pintype "passive"))
      (node (ref "U10") (pin "9") (pinfunction "TRACK/SS_9") (pintype "passive"))
    )
    (net (code "32") (name "Net-(U10-RT)") (class "Default")
      (node (ref "R66") (pin "2") (pinfunction "2_2") (pintype "passive"))
      (node (ref "U10") (pin "12") (pinfunction "RT_12") (pintype "passive"))
    )
    (net (code "33") (name "Net-(U10-RUN)") (class "Default")
      (node (ref "C54") (pin "2") (pinfunction "2_2") (pintype "passive"))
      (node (ref "R37") (pin "2") (pinfunction "2_2") (pintype "passive"))
      (node (ref "U10") (pin "13") (pinfunction "RUN_13") (pintype "passive"))
      (node (ref "U10") (pin "14") (pinfunction "SVIN_14") (pintype "passive"))
    )
    (net (code "34") (name "Net-(U10-TMON)") (class "Default")
      (node (ref "TMON1") (pin "1") (pinfunction "1_1") (pintype "passive"))
      (node (ref "U10") (pin "5") (pinfunction "TMON_5") (pintype "passive"))
    )
    (net (code "35") (name "Net-(U10-TSET)") (class "Default")
      (node (ref "R62") (pin "1") (pinfunction "1_1") (pintype "passive"))
      (node (ref "R68") (pin "1") (pinfunction "1_1") (pintype "passive"))
      (node (ref "U10") (pin "4") (pinfunction "TSET_4") (pintype "passive"))
    )
    (net (code "36") (name "Net-(U10-VON)") (class "Default")
      (node (ref "C52") (pin "1") (pinfunction "1_1") (pintype "passive"))
      (node (ref "L15") (pin "1") (pinfunction "1_1") (pintype "passive"))
      (node (ref "U10") (pin "19") (pinfunction "SW_19") (pintype "passive"))
      (node (ref "U10") (pin "20") (pinfunction "SW_20") (pintype "passive"))
      (node (ref "U10") (pin "3") (pinfunction "VON_3") (pintype "passive"))
    )
    (net (code "37") (name "Net-(U11-BOOST)") (class "Default")
      (node (ref "C53") (pin "2") (pinfunction "2_2") (pintype "passive"))
      (node (ref "U11") (pin "1") (pinfunction "BOOST_1") (pintype "passive"))
    )
    (net (code "38") (name "Net-(U11-FB)") (class "Default")
      (node (ref "C68") (pin "1") (pinfunction "1_1") (pintype "passive"))
      (node (ref "R61") (pin "1") (pinfunction "1_1") (pintype "passive"))
      (node (ref "R65") (pin "2") (pinfunction "2_2") (pintype "passive"))
      (node (ref "U11") (pin "10") (pinfunction "FB_10") (pintype "passive"))
    )
    (net (code "39") (name "Net-(U11-IMONin)") (class "Default")
      (node (ref "R74") (pin "2") (pinfunction "2_2") (pintype "passive"))
      (node (ref "U11") (pin "7") (pinfunction "IMONin_7") (pintype "passive"))
    )
    (net (code "40") (name "Net-(U11-IMONout)") (class "Default")
      (node (ref "R73") (pin "2") (pinfunction "2_2") (pintype "passive"))
      (node (ref "U11") (pin "8") (pinfunction "IMONout_8") (pintype "passive"))
    )
    (net (code "41") (name "Net-(U11-INTVCC)") (class "Default")
      (node (ref "C59") (pin "2") (pinfunction "2_2") (pintype "passive"))
      (node (ref "R63") (pin "2") (pinfunction "2_2") (pintype "passive"))
      (node (ref "U11") (pin "11") (pinfunction "ITH_11") (pintype "passive"))
      (node (ref "U11") (pin "2") (pinfunction "INTVCC_2") (pintype "passive"))
      (node (ref "U11") (pin "9") (pinfunction "TRACK/SS_9") (pintype "passive"))
      (node (ref "U18") (pin "5") (pinfunction "Vcc_5") (pintype "power_in"))
    )
    (net (code "42") (name "Net-(U11-MODE{slash}SYNC)") (class "Default")
      (node (ref "U11") (pin "17") (pinfunction "MODE/SYNC_17") (pintype "passive"))
      (node (ref "U18") (pin "1") (pinfunction "Out_1") (pintype "passive"))
    )
    (net (code "43") (name "Net-(U11-PGND{slash}EXPPAD)") (class "Default")
      (node (ref "C56") (pin "2") (pinfunction "2_2") (pintype "passive"))
      (node (ref "R109") (pin "2") (pinfunction "2_2") (pintype "passive"))
      (node (ref "R65") (pin "1") (pinfunction "1_1") (pintype "passive"))
      (node (ref "R67") (pin "1") (pinfunction "1_1") (pintype "passive"))
      (node (ref "R69") (pin "2") (pinfunction "2_2") (pintype "passive"))
      (node (ref "R73") (pin "1") (pinfunction "1_1") (pintype "passive"))
      (node (ref "R74") (pin "1") (pinfunction "1_1") (pintype "passive"))
      (node (ref "U11") (pin "21") (pinfunction "PGND/EXPPAD_21") (pintype "passive"))
      (node (ref "U11") (pin "6") (pinfunction "SGND_6") (pintype "passive"))
      (node (ref "U18") (pin "2") (pinfunction "A_2") (pintype "passive"))
    )
    (net (code "44") (name "Net-(U11-RT)") (class "Default")
      (node (ref "R67") (pin "2") (pinfunction "2_2") (pintype "passive"))
      (node (ref "U11") (pin "12") (pinfunction "RT_12") (pintype "passive"))
    )
    (net (code "45") (name "Net-(U11-RUN)") (class "Default")
      (node (ref "C50") (pin "2") (pinfunction "2_2") (pintype "passive"))
      (node (ref "R36") (pin "1") (pinfunction "1_1") (pintype "passive"))
      (node (ref "U11") (pin "13") (pinfunction "RUN_13") (pintype "passive"))
      (node (ref "U11") (pin "14") (pinfunction "SVIN_14") (pintype "passive"))
    )
    (net (code "46") (name "Net-(U11-TMON)") (class "Default")
      (node (ref "TMON2") (pin "1") (pinfunction "1_1") (pintype "passive"))
      (node (ref "U11") (pin "5") (pinfunction "TMON_5") (pintype "passive"))
    )
    (net (code "47") (name "Net-(U11-TSET)") (class "Default")
      (node (ref "R63") (pin "1") (pinfunction "1_1") (pintype "passive"))
      (node (ref "R69") (pin "1") (pinfunction "1_1") (pintype "passive"))
      (node (ref "U11") (pin "4") (pinfunction "TSET_4") (pintype "passive"))
    )
    (net (code "48") (name "Net-(U11-VON)") (class "Default")
      (node (ref "C53") (pin "1") (pinfunction "1_1") (pintype "passive"))
      (node (ref "L16") (pin "1") (pinfunction "1_1") (pintype "passive"))
      (node (ref "U11") (pin "19") (pinfunction "SW_19") (pintype "passive"))
      (node (ref "U11") (pin "20") (pinfunction "SW_20") (pintype "passive"))
      (node (ref "U11") (pin "3") (pinfunction "VON_3") (pintype "passive"))
    )
    (net (code "49") (name "Net-(U12-ADJ)") (class "Default")
      (node (ref "R27") (pin "2") (pinfunction "2_2") (pintype "passive"))
      (node (ref "R28") (pin "1") (pinfunction "1_1") (pintype "passive"))
      (node (ref "U12") (pin "2") (pinfunction "ADJ_2") (pintype "passive"))
    )
    (net (code "50") (name "Net-(U12-BYP)") (class "Default")
      (node (ref "C109") (pin "1") (pinfunction "1_1") (pintype "passive"))
      (node (ref "U12") (pin "3") (pinfunction "BYP_3") (pintype "passive"))
    )
    (net (code "51") (name "Net-(U12-IN)") (class "Default")
      (node (ref "C98") (pin "1") (pinfunction "1_1") (pintype "passive"))
      (node (ref "L10") (pin "2") (pinfunction "2_2") (pintype "passive"))
      (node (ref "U12") (pin "8") (pinfunction "IN_8") (pintype "power_in"))
    )
    (net (code "52") (name "Net-(U12-SHDN)") (class "Default")
      (node (ref "C95") (pin "1") (pinfunction "1_1") (pintype "passive"))
      (node (ref "R35") (pin "2") (pinfunction "2_2") (pintype "passive"))
      (node (ref "U12") (pin "5") (pinfunction "SHDN_5") (pintype "passive"))
      (node (ref "U13") (pin "6") (pinfunction "SHDN_6") (pintype "passive"))
      (node (ref "U14") (pin "5") (pinfunction "SHDN_5") (pintype "passive"))
    )
    (net (code "53") (name "Net-(U13-ILim2)") (class "Default")
      (node (ref "C101") (pin "2") (pinfunction "2_2") (pintype "passive"))
      (node (ref "L11") (pin "1") (pinfunction "1_1") (pintype "passive"))
      (node (ref "R38") (pin "2") (pinfunction "2_2") (pintype "passive"))
      (node (ref "U13") (pin "1") (pinfunction "IN_1") (pintype "power_in"))
      (node (ref "U13") (pin "2") (pinfunction "ILim2_2") (pintype "passive"))
      (node (ref "U13") (pin "8") (pinfunction "IN_8") (pintype "power_in"))
    )
    (net (code "54") (name "Net-(U13-ILim4)") (class "Default")
      (node (ref "R38") (pin "1") (pinfunction "1_1") (pintype "passive"))
      (node (ref "U13") (pin "7") (pinfunction "ILim4_7") (pintype "passive"))
    )
    (net (code "55") (name "Net-(U13-SENSE)") (class "Default")
      (node (ref "R39") (pin "2") (pinfunction "2_2") (pintype "passive"))
      (node (ref "R40") (pin "1") (pinfunction "1_1") (pintype "passive"))
      (node (ref "U13") (pin "4") (pinfunction "SENSE_4") (pintype "power_in"))
    )
    (net (code "56") (name "Net-(U14-ADJ)") (class "Default")
      (node (ref "R41") (pin "2") (pinfunction "2_2") (pintype "passive"))
      (node (ref "R42") (pin "1") (pinfunction "1_1") (pintype "passive"))
      (node (ref "U14") (pin "2") (pinfunction "ADJ_2") (pintype "passive"))
    )
    (net (code "57") (name "Net-(U14-BYP)") (class "Default")
      (node (ref "C103") (pin "1") (pinfunction "1_1") (pintype "passive"))
      (node (ref "U14") (pin "3") (pinfunction "BYP_3") (pintype "passive"))
    )
    (net (code "58") (name "Net-(U14-IN)") (class "Default")
      (node (ref "C111") (pin "1") (pinfunction "1_1") (pintype "passive"))
      (node (ref "L12") (pin "2") (pinfunction "2_2") (pintype "passive"))
      (node (ref "U14") (pin "8") (pinfunction "IN_8") (pintype "power_in"))
    )
    (net (code "59") (name "Net-(U18-+)") (class "Default")
      (node (ref "R71") (pin "1") (pinfunction "1_1") (pintype "passive"))
      (node (ref "R75") (pin "1") (pinfunction "1_1") (pintype "passive"))
      (node (ref "U18") (pin "3") (pinfunction "+_3") (pintype "passive"))
    )
    (net (code "60") (name "Net-(U19-ADJ)") (class "Default")
      (node (ref "R85") (pin "2") (pinfunction "2_2") (pintype "passive"))
      (node (ref "R86") (pin "1") (pinfunction "1_1") (pintype "passive"))
      (node (ref "U19") (pin "2") (pinfunction "ADJ_2") (pintype "passive"))
    )
    (net (code "61") (name "Net-(U19-BYP)") (class "Default")
      (node (ref "C82") (pin "1") (pinfunction "1_1") (pintype "passive"))
      (node (ref "U19") (pin "3") (pinfunction "BYP_3") (pintype "passive"))
    )
    (net (code "62") (name "Net-(U19-IN)") (class "Default")
      (node (ref "C96") (pin "1") (pinfunction "1_1") (pintype "passive"))
      (node (ref "L17") (pin "2") (pinfunction "2_2") (pintype "passive"))
      (node (ref "U19") (pin "8") (pinfunction "IN_8") (pintype "power_in"))
    )
    (net (code "63") (name "Net-(U19-SHDN)") (class "Default")
      (node (ref "C93") (pin "2") (pinfunction "2_2") (pintype "passive"))
      (node (ref "R33") (pin "2") (pinfunction "2_2") (pintype "passive"))
      (node (ref "R34") (pin "1") (pinfunction "1_1") (pintype "passive"))
      (node (ref "U19") (pin "5") (pinfunction "SHDN_5") (pintype "passive"))
    )
    (net (code "64") (name "unconnected-(J4-Pad2)") (class "Default")
      (node (ref "J4") (pin "2") (pinfunction "2_2") (pintype "passive"))
    )
    (net (code "65") (name "unconnected-(U10-PGOOD-Pad18)") (class "Default")
      (node (ref "U10") (pin "18") (pinfunction "PGOOD_18") (pintype "passive+no_connect"))
    )
    (net (code "66") (name "unconnected-(U11-PGOOD-Pad18)") (class "Default")
      (node (ref "U11") (pin "18") (pinfunction "PGOOD_18") (pintype "passive+no_connect"))
    )
    (net (code "67") (name "unconnected-(U12-NC-Pad6)") (class "Default")
      (node (ref "U12") (pin "6") (pinfunction "NC_6") (pintype "passive"))
    )
    (net (code "68") (name "unconnected-(U12-NC-Pad7)") (class "Default")
      (node (ref "U12") (pin "7") (pinfunction "NC_7") (pintype "passive"))
    )
    (net (code "69") (name "unconnected-(U14-NC-Pad6)") (class "Default")
      (node (ref "U14") (pin "6") (pinfunction "NC_6") (pintype "passive"))
    )
    (net (code "70") (name "unconnected-(U14-NC-Pad7)") (class "Default")
      (node (ref "U14") (pin "7") (pinfunction "NC_7") (pintype "passive"))
    )
    (net (code "71") (name "unconnected-(U19-NC-Pad6)") (class "Default")
      (node (ref "U19") (pin "6") (pinfunction "NC_6") (pintype "passive"))
    )
    (net (code "72") (name "unconnected-(U19-NC-Pad7)") (class "Default")
      (node (ref "U19") (pin "7") (pinfunction "NC_7") (pintype "passive"))
    )
  )
)
